# TYPEC.net
KiCad netlist of a schematic drawn in Altium Designer
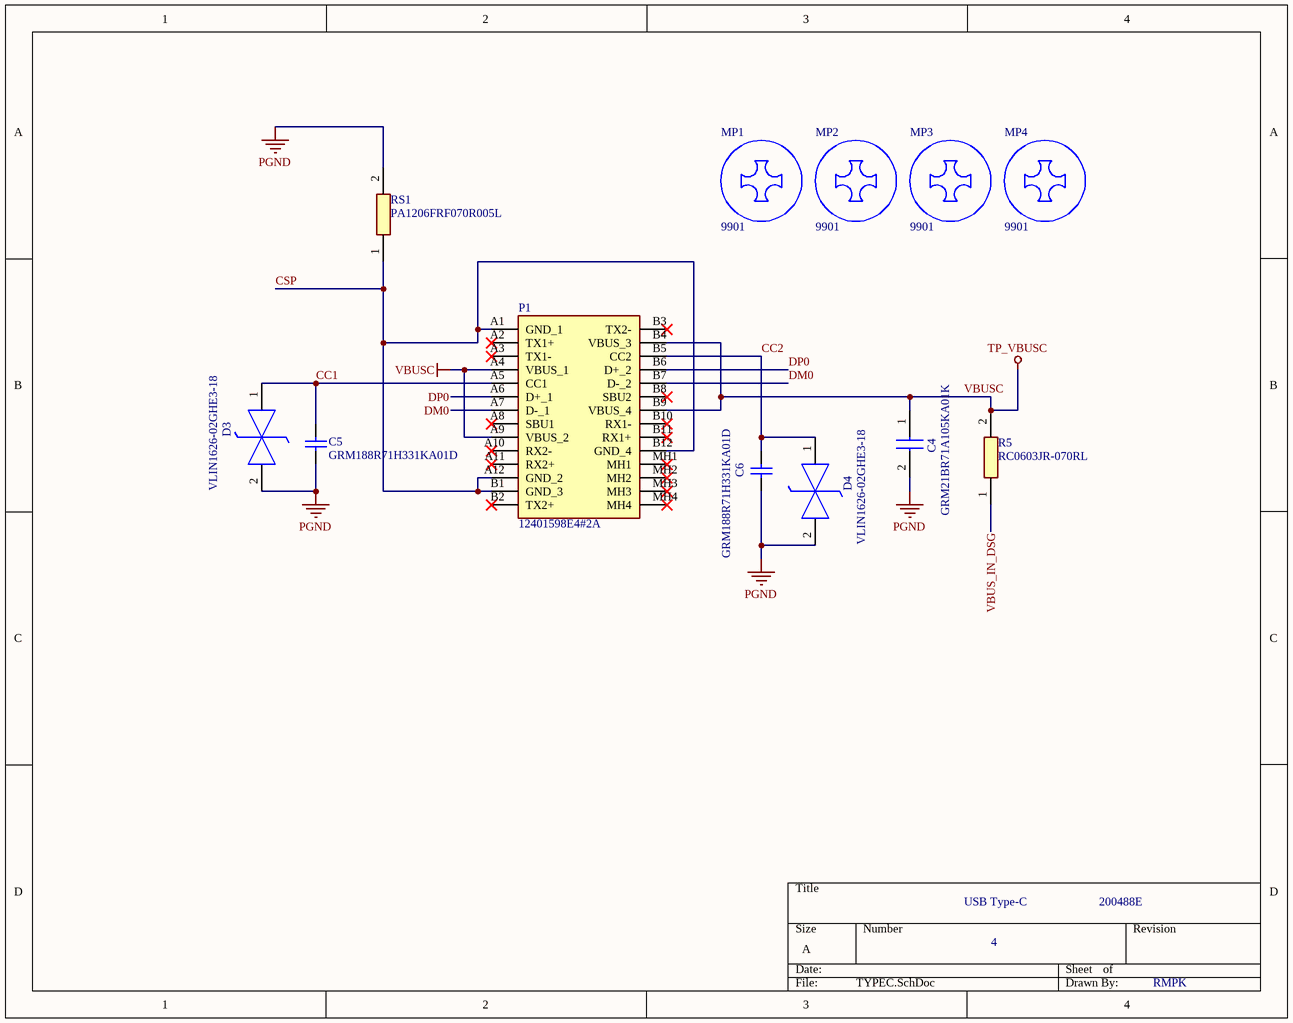
[diagram p0: TYPEC.SchDoc]

(export (version "E")
  (design (tool "Eeschema 10.0.6"))
  (components
    (comp (ref "C4")
      (value "GRM21BR71A105KA01K")
      (footprint "SamacSys:CAPC2012X145N")
      (description "Capacitor")
      (fields (field (name "MOUSER PART NUMBER") "81-GRM40X105K10K"))
      (libsource (lib "*") (part "GRM21BR71A105KA01K"))
    )
    (comp (ref "C5")
      (value "GRM188R71H331KA01D")
      (footprint "CAPC1608X90X35NL10T15")
      (fields (field (name "MANUFACTURER") "Murata"))
      (libsource (lib "Altium Content Vault") (part "CAP"))
    )
    (comp (ref "C6")
      (value "GRM188R71H331KA01D")
      (footprint "CAPC1608X90X35NL10T15")
      (fields (field (name "MANUFACTURER") "Murata"))
      (libsource (lib "Altium Content Vault") (part "CAP"))
    )
    (comp (ref "D3")
      (value "VLIN1626-02GHE3-18")
      (footprint "SamacSys:SOD2713X115N")
      (description "Diode ESD (Bi-directional)")
      (fields (field (name "MOUSER PART NUMBER") "78-VLIN1626-02GHE318"))
      (libsource (lib "*") (part "VLIN1626-02GHE3-18"))
    )
    (comp (ref "D4")
      (value "VLIN1626-02GHE3-18")
      (footprint "SamacSys:SOD2713X115N")
      (description "Diode ESD (Bi-directional)")
      (fields (field (name "MOUSER PART NUMBER") "78-VLIN1626-02GHE318"))
      (libsource (lib "*") (part "VLIN1626-02GHE3-18"))
    )
    (comp (ref "MP1")
      (value "9901")
      (footprint "FP-9901-MFG")
      (description "MACHINE SCREW PAN PHILLIPS 4-40")
      (libsource (lib "Altium Content Vault") (part "00aa4b1e0213c22a4cfa0708b50314e"))
    )
    (comp (ref "MP2")
      (value "9901")
      (footprint "FP-9901-MFG")
      (description "MACHINE SCREW PAN PHILLIPS 4-40")
      (libsource (lib "Altium Content Vault") (part "00aa4b1e0213c22a4cfa0708b50314e"))
    )
    (comp (ref "MP3")
      (value "9901")
      (footprint "FP-9901-MFG")
      (description "MACHINE SCREW PAN PHILLIPS 4-40")
      (libsource (lib "Altium Content Vault") (part "00aa4b1e0213c22a4cfa0708b50314e"))
    )
    (comp (ref "MP4")
      (value "9901")
      (footprint "FP-9901-MFG")
      (description "MACHINE SCREW PAN PHILLIPS 4-40")
      (libsource (lib "Altium Content Vault") (part "00aa4b1e0213c22a4cfa0708b50314e"))
    )
    (comp (ref "P1")
      (value "12401598E4#2A")
      (footprint "SamacSys:12401598E42A")
      (description "Connector")
      (fields (field (name "MOUSER PART NUMBER") "523-12401598E4#2A"))
      (libsource (lib "*") (part "12401598E4#2A"))
    )
    (comp (ref "R5")
      (value "RC0603JR-070RL")
      (footprint "SamacSys:RESC1608X55N")
      (description "Resistor")
      (fields (field (name "MOUSER PART NUMBER") "603-RC0603JR-070RL"))
      (libsource (lib "*") (part "RC0603JR-070RL"))
    )
    (comp (ref "RS1")
      (value "PA1206FRF070R005L")
      (footprint "SamacSys:RESC3216X65N")
      (description "Resistor")
      (libsource (lib "*") (part "PA1206FRF070R005L"))
    )
  )
  (nets
    (net (code "1") (name "/CC1") (class "Default")
      (node (ref "C5") (pin "2") (pinfunction "2_2") (pintype "passive"))
      (node (ref "D3") (pin "1") (pinfunction "K1_1") (pintype "passive"))
      (node (ref "P1") (pin "A5") (pinfunction "CC1_A5") (pintype "passive"))
    )
    (net (code "2") (name "/CC2") (class "Default")
      (node (ref "C6") (pin "2") (pinfunction "2_2") (pintype "passive"))
      (node (ref "D4") (pin "1") (pinfunction "K1_1") (pintype "passive"))
      (node (ref "P1") (pin "B5") (pinfunction "CC2_B5") (pintype "passive"))
    )
    (net (code "3") (name "/CSP") (class "Default")
      (node (ref "P1") (pin "A1") (pinfunction "GND_1_A1") (pintype "passive"))
      (node (ref "P1") (pin "A12") (pinfunction "GND_2_A12") (pintype "passive"))
      (node (ref "P1") (pin "B1") (pinfunction "GND_3_B1") (pintype "passive"))
      (node (ref "P1") (pin "B12") (pinfunction "GND_4_B12") (pintype "passive"))
      (node (ref "RS1") (pin "1") (pinfunction "1_1") (pintype "passive"))
    )
    (net (code "4") (name "/DM0") (class "Default")
      (node (ref "P1") (pin "A7") (pinfunction "D-_1_A7") (pintype "passive"))
      (node (ref "P1") (pin "B7") (pinfunction "D-_2_B7") (pintype "passive"))
    )
    (net (code "5") (name "/DP0") (class "Default")
      (node (ref "P1") (pin "A6") (pinfunction "D+_1_A6") (pintype "passive"))
      (node (ref "P1") (pin "B6") (pinfunction "D+_2_B6") (pintype "passive"))
    )
    (net (code "6") (name "/VBUS_IN_DSG") (class "Default")
      (node (ref "R5") (pin "1") (pinfunction "1_1") (pintype "passive"))
    )
    (net (code "7") (name "PGND") (class "Default")
      (node (ref "C4") (pin "2") (pinfunction "2_2") (pintype "passive"))
      (node (ref "C5") (pin "1") (pinfunction "1_1") (pintype "passive"))
      (node (ref "C6") (pin "1") (pinfunction "1_1") (pintype "passive"))
      (node (ref "D3") (pin "2") (pinfunction "K2_2") (pintype "passive"))
      (node (ref "D4") (pin "2") (pinfunction "K2_2") (pintype "passive"))
      (node (ref "RS1") (pin "2") (pinfunction "2_2") (pintype "passive"))
    )
    (net (code "8") (name "TP_VBUSC") (class "Default")
      (node (ref "C4") (pin "1") (pinfunction "1_1") (pintype "passive"))
      (node (ref "P1") (pin "A4") (pinfunction "VBUS_1_A4") (pintype "passive"))
      (node (ref "P1") (pin "A9") (pinfunction "VBUS_2_A9") (pintype "passive"))
      (node (ref "P1") (pin "B4") (pinfunction "VBUS_3_B4") (pintype "passive"))
      (node (ref "P1") (pin "B9") (pinfunction "VBUS_4_B9") (pintype "passive"))
      (node (ref "R5") (pin "2") (pinfunction "2_2") (pintype "passive"))
    )
    (net (code "9") (name "unconnected-(P1-PadMH1)") (class "Default")
      (node (ref "P1") (pin "MH1") (pinfunction "MH1_MH1") (pintype "passive+no_connect"))
    )
    (net (code "10") (name "unconnected-(P1-PadMH2)") (class "Default")
      (node (ref "P1") (pin "MH2") (pinfunction "MH2_MH2") (pintype "passive+no_connect"))
    )
    (net (code "11") (name "unconnected-(P1-PadMH3)") (class "Default")
      (node (ref "P1") (pin "MH3") (pinfunction "MH3_MH3") (pintype "passive+no_connect"))
    )
    (net (code "12") (name "unconnected-(P1-PadMH4)") (class "Default")
      (node (ref "P1") (pin "MH4") (pinfunction "MH4_MH4") (pintype "passive+no_connect"))
    )
    (net (code "13") (name "unconnected-(P1-RX1+-PadB11)") (class "Default")
      (node (ref "P1") (pin "B11") (pinfunction "RX1+_B11") (pintype "passive+no_connect"))
    )
    (net (code "14") (name "unconnected-(P1-RX1--PadB10)") (class "Default")
      (node (ref "P1") (pin "B10") (pinfunction "RX1-_B10") (pintype "passive+no_connect"))
    )
    (net (code "15") (name "unconnected-(P1-RX2+-PadA11)") (class "Default")
      (node (ref "P1") (pin "A11") (pinfunction "RX2+_A11") (pintype "passive+no_connect"))
    )
    (net (code "16") (name "unconnected-(P1-RX2--PadA10)") (class "Default")
      (node (ref "P1") (pin "A10") (pinfunction "RX2-_A10") (pintype "passive+no_connect"))
    )
    (net (code "17") (name "unconnected-(P1-SBU1-PadA8)") (class "Default")
      (node (ref "P1") (pin "A8") (pinfunction "SBU1_A8") (pintype "passive+no_connect"))
    )
    (net (code "18") (name "unconnected-(P1-SBU2-PadB8)") (class "Default")
      (node (ref "P1") (pin "B8") (pinfunction "SBU2_B8") (pintype "passive+no_connect"))
    )
    (net (code "19") (name "unconnected-(P1-TX1+-PadA2)") (class "Default")
      (node (ref "P1") (pin "A2") (pinfunction "TX1+_A2") (pintype "passive+no_connect"))
    )
    (net (code "20") (name "unconnected-(P1-TX1--PadA3)") (class "Default")
      (node (ref "P1") (pin "A3") (pinfunction "TX1-_A3") (pintype "passive+no_connect"))
    )
    (net (code "21") (name "unconnected-(P1-TX2+-PadB2)") (class "Default")
      (node (ref "P1") (pin "B2") (pinfunction "TX2+_B2") (pintype "passive+no_connect"))
    )
    (net (code "22") (name "unconnected-(P1-TX2--PadB3)") (class "Default")
      (node (ref "P1") (pin "B3") (pinfunction "TX2-_B3") (pintype "passive+no_connect"))
    )
  )
)
